# SupplyBoxTest.net
KiCad netlist of a schematic drawn in Altium Designer
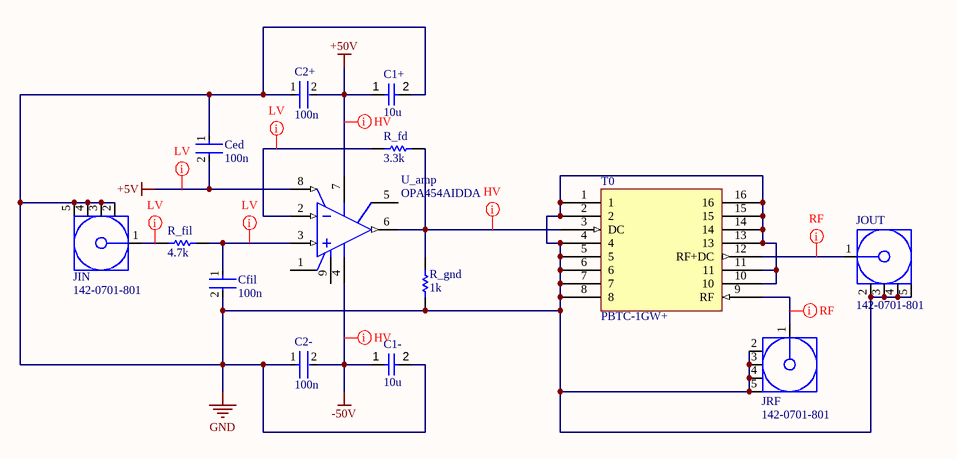
[diagram p0: SupplyBoxTest.SchDoc]

(export (version "E")
  (design (tool "Eeschema 10.0.6"))
  (components
    (comp (ref "C1+")
      (value "10u")
      (footprint "RAHV1100M1UCC8002E-Footprint-1")
      (libsource (lib "Li-Ren Liu") (part "CAP-NP-2"))
    )
    (comp (ref "C1-")
      (value "10u")
      (footprint "RAHV1100M1UCC8002E-Footprint-1")
      (libsource (lib "Li-Ren Liu") (part "CAP-NP-2"))
    )
    (comp (ref "C2+")
      (value "100n")
      (footprint "FP-CC0805-0_85-MFG")
      (description "CAP CER 0.1UF 25V X7R 0805")
      (fields (field (name "MANUFACTURER PART NUMBER") "CC0805KRX7R8BB104") (field (name "TOLERANCE") "0.1"))
      (libsource (lib "Altium Content Vault") (part "11868f565c42a9108669ba33697ecf6"))
    )
    (comp (ref "C2-")
      (value "100n")
      (footprint "FP-CC0805-0_85-MFG")
      (description "CAP CER 0.1UF 25V X7R 0805")
      (fields (field (name "MANUFACTURER PART NUMBER") "CC0805KRX7R8BB104") (field (name "TOLERANCE") "0.1"))
      (libsource (lib "Altium Content Vault") (part "11868f565c42a9108669ba33697ecf6"))
    )
    (comp (ref "Ced")
      (value "100n")
      (footprint "FP-CC0805-0_85-MFG")
      (description "CAP CER 0.1UF 25V X7R 0805")
      (fields (field (name "MANUFACTURER PART NUMBER") "CC0805KRX7R8BB104") (field (name "TOLERANCE") "0.1"))
      (libsource (lib "Altium Content Vault") (part "11868f565c42a9108669ba33697ecf6"))
    )
    (comp (ref "Cfil")
      (value "100n")
      (footprint "FP-CC0805-0_85-MFG")
      (description "CAP CER 0.1UF 25V X7R 0805")
      (fields (field (name "MANUFACTURER PART NUMBER") "CC0805KRX7R8BB104") (field (name "TOLERANCE") "0.1"))
      (libsource (lib "Altium Content Vault") (part "11868f565c42a9108669ba33697ecf6"))
    )
    (comp (ref "JIN")
      (value "142-0701-801")
      (footprint "CINC-142-0701-801_V")
      (description "SMA End Launch Jack Receptacle, 50 Ohm, 0 to 18 GHz, -65 to 165 degC, 5-Pin SMD, RoHS, Bulk")
      (fields (field (name "MANUFACTURER") "EmersonConnectivitySolutions"))
      (libsource (lib "Altium Content Vault") (part "CN-S-4F-RF5"))
    )
    (comp (ref "JOUT")
      (value "142-0701-801")
      (footprint "CINC-142-0701-801_V")
      (description "SMA End Launch Jack Receptacle, 50 Ohm, 0 to 18 GHz, -65 to 165 degC, 5-Pin SMD, RoHS, Bulk")
      (fields (field (name "MANUFACTURER") "EmersonConnectivitySolutions"))
      (libsource (lib "Altium Content Vault") (part "CN-S-4F-RF5"))
    )
    (comp (ref "JRF")
      (value "142-0701-801")
      (footprint "CINC-142-0701-801_V")
      (description "SMA End Launch Jack Receptacle, 50 Ohm, 0 to 18 GHz, -65 to 165 degC, 5-Pin SMD, RoHS, Bulk")
      (fields (field (name "MANUFACTURER") "EmersonConnectivitySolutions"))
      (libsource (lib "Altium Content Vault") (part "CN-S-4F-RF5"))
    )
    (comp (ref "R_fd")
      (value "3.3k")
      (footprint "RESC2013X60X35ML10T20")
      (description "Chip Resistor, 3.3 KOhm, +/- 1%, 0.125 W, -55 to 155 degC, 0805 (2012 Metric), RoHS, Tape and Reel")
      (fields (field (name "TOLERANCE") "1%") (field (name "MANUFACTURER") "Yageo"))
      (libsource (lib "Altium Content Vault") (part "RES-2"))
    )
    (comp (ref "R_fil")
      (value "4.7k")
      (footprint "RESC2013X60X35NL10T20")
      (description "Chip Resistor, 47 KOhm, +/- 1%, 0.125 W, -55 to 155 degC, 0805 (2012 Metric), RoHS, Tape and Reel")
      (fields (field (name "MANUFACTURER") "Yageo"))
      (libsource (lib "Altium Content Vault") (part "RES-2"))
    )
    (comp (ref "R_gnd")
      (value "1k")
      (footprint "RESC2013X60X35ML10T20")
      (description "Chip Resistor, 1 KOhm, +/- 1%, 125 mW, -55 to 155 degC, 0805 (2012 Metric), RoHS, Tape and Reel")
      (fields (field (name "TOLERANCE") "1%") (field (name "MANUFACTURER") "Yageo"))
      (libsource (lib "Altium Content Vault") (part "RES-2"))
    )
    (comp (ref "T0")
      (value "PBTC-1GW+")
      (footprint "PBTC-1GW+")
      (description "Monitor TEE DC Block, 0.1MHz Min, 1000MHz Max, 1dB Insertion Loss-Max")
      (libsource (lib "Li-Ren Liu") (part "PBTC-1GW+-Symbol-1"))
    )
    (comp (ref "U_amp")
      (value "OPA454AIDDA")
      (footprint "DDA0008C_L")
      (fields (field (name "MANUFACTURER") "Texas Instruments"))
      (libsource (lib "Altium Content Vault") (part "TI-OPA454-DDA8"))
    )
  )
  (nets
    (net (code "1") (name "+5V") (class "Default")
      (node (ref "Ced") (pin "2") (pinfunction "2_2") (pintype "passive"))
      (node (ref "U_amp") (pin "8") (pinfunction "E/D_8") (pintype "input"))
    )
    (net (code "2") (name "+50V") (class "Default")
      (node (ref "C1+") (pin "1") (pinfunction "1_1") (pintype "passive"))
      (node (ref "C2+") (pin "2") (pinfunction "2_2") (pintype "passive"))
      (node (ref "U_amp") (pin "7") (pinfunction "V+_7") (pintype "power_in"))
    )
    (net (code "3") (name "-50V") (class "Default")
      (node (ref "C1-") (pin "1") (pinfunction "1_1") (pintype "passive"))
      (node (ref "C2-") (pin "2") (pinfunction "2_2") (pintype "passive"))
      (node (ref "U_amp") (pin "4") (pinfunction "V-_4") (pintype "power_in"))
    )
    (net (code "4") (name "GND") (class "Default")
      (node (ref "C1+") (pin "2") (pinfunction "2_2") (pintype "passive"))
      (node (ref "C1-") (pin "2") (pinfunction "2_2") (pintype "passive"))
      (node (ref "C2+") (pin "1") (pinfunction "1_1") (pintype "passive"))
      (node (ref "C2-") (pin "1") (pinfunction "1_1") (pintype "passive"))
      (node (ref "Ced") (pin "1") (pinfunction "1_1") (pintype "passive"))
      (node (ref "Cfil") (pin "2") (pinfunction "2_2") (pintype "passive"))
      (node (ref "JIN") (pin "2") (pinfunction "2_2") (pintype "passive"))
      (node (ref "JIN") (pin "3") (pinfunction "3_3") (pintype "passive"))
      (node (ref "JIN") (pin "4") (pinfunction "4_4") (pintype "passive"))
      (node (ref "JIN") (pin "5") (pinfunction "5_5") (pintype "passive"))
      (node (ref "JOUT") (pin "2") (pinfunction "2_2") (pintype "passive"))
      (node (ref "JOUT") (pin "3") (pinfunction "3_3") (pintype "passive"))
      (node (ref "JOUT") (pin "4") (pinfunction "4_4") (pintype "passive"))
      (node (ref "JOUT") (pin "5") (pinfunction "5_5") (pintype "passive"))
      (node (ref "JRF") (pin "2") (pinfunction "2_2") (pintype "passive"))
      (node (ref "JRF") (pin "3") (pinfunction "3_3") (pintype "passive"))
      (node (ref "JRF") (pin "4") (pinfunction "4_4") (pintype "passive"))
      (node (ref "JRF") (pin "5") (pinfunction "5_5") (pintype "passive"))
      (node (ref "R_gnd") (pin "1") (pinfunction "1_1") (pintype "passive"))
      (node (ref "T0") (pin "1") (pinfunction "1_1") (pintype "passive"))
      (node (ref "T0") (pin "10") (pinfunction "10_10") (pintype "passive"))
      (node (ref "T0") (pin "11") (pinfunction "11_11") (pintype "passive"))
      (node (ref "T0") (pin "13") (pinfunction "13_13") (pintype "passive"))
      (node (ref "T0") (pin "14") (pinfunction "14_14") (pintype "passive"))
      (node (ref "T0") (pin "15") (pinfunction "15_15") (pintype "passive"))
      (node (ref "T0") (pin "16") (pinfunction "16_16") (pintype "passive"))
      (node (ref "T0") (pin "2") (pinfunction "2_2") (pintype "passive"))
      (node (ref "T0") (pin "4") (pinfunction "4_4") (pintype "passive"))
      (node (ref "T0") (pin "5") (pinfunction "5_5") (pintype "passive"))
      (node (ref "T0") (pin "6") (pinfunction "6_6") (pintype "passive"))
      (node (ref "T0") (pin "7") (pinfunction "7_7") (pintype "passive"))
      (node (ref "T0") (pin "8") (pinfunction "8_8") (pintype "passive"))
    )
    (net (code "5") (name "Net-(JIN-Pad1)") (class "Default")
      (node (ref "JIN") (pin "1") (pinfunction "1_1") (pintype "passive"))
      (node (ref "R_fil") (pin "1") (pinfunction "1_1") (pintype "passive"))
    )
    (net (code "6") (name "Net-(T0-DC)") (class "Default")
      (node (ref "R_fd") (pin "2") (pinfunction "2_2") (pintype "passive"))
      (node (ref "R_gnd") (pin "2") (pinfunction "2_2") (pintype "passive"))
      (node (ref "T0") (pin "3") (pinfunction "DC_3") (pintype "input"))
      (node (ref "U_amp") (pin "6") (pinfunction "OUT_6") (pintype "output"))
    )
    (net (code "7") (name "Net-(T0-RF)") (class "Default")
      (node (ref "JRF") (pin "1") (pinfunction "1_1") (pintype "passive"))
      (node (ref "T0") (pin "9") (pinfunction "RF_9") (pintype "input"))
    )
    (net (code "8") (name "Net-(T0-RF+DC)") (class "Default")
      (node (ref "JOUT") (pin "1") (pinfunction "1_1") (pintype "passive"))
      (node (ref "T0") (pin "12") (pinfunction "RF+DC_12") (pintype "output"))
    )
    (net (code "9") (name "Net-(U_amp-IN+)") (class "Default")
      (node (ref "Cfil") (pin "1") (pinfunction "1_1") (pintype "passive"))
      (node (ref "R_fil") (pin "2") (pinfunction "2_2") (pintype "passive"))
      (node (ref "U_amp") (pin "3") (pinfunction "IN+_3") (pintype "input"))
    )
    (net (code "10") (name "Net-(U_amp-IN-)") (class "Default")
      (node (ref "R_fd") (pin "1") (pinfunction "1_1") (pintype "passive"))
      (node (ref "U_amp") (pin "2") (pinfunction "IN-_2") (pintype "input"))
    )
    (net (code "11") (name "unconnected-(U_amp-EP-Pad9)") (class "Default")
      (node (ref "U_amp") (pin "9") (pinfunction "EP_9") (pintype "power_in"))
    )
    (net (code "12") (name "unconnected-(U_amp-E{slash}D_COM-Pad1)") (class "Default")
      (node (ref "U_amp") (pin "1") (pinfunction "E/D_COM_1") (pintype "power_in"))
    )
    (net (code "13") (name "unconnected-(U_amp-STATUS_FLAG-Pad5)") (class "Default")
      (node (ref "U_amp") (pin "5") (pinfunction "STATUS_FLAG_5") (pintype "open_collector"))
    )
  )
)
